# tricorder-teensy-mk-1_10.net
KiCad netlist of a schematic drawn in EAGLE
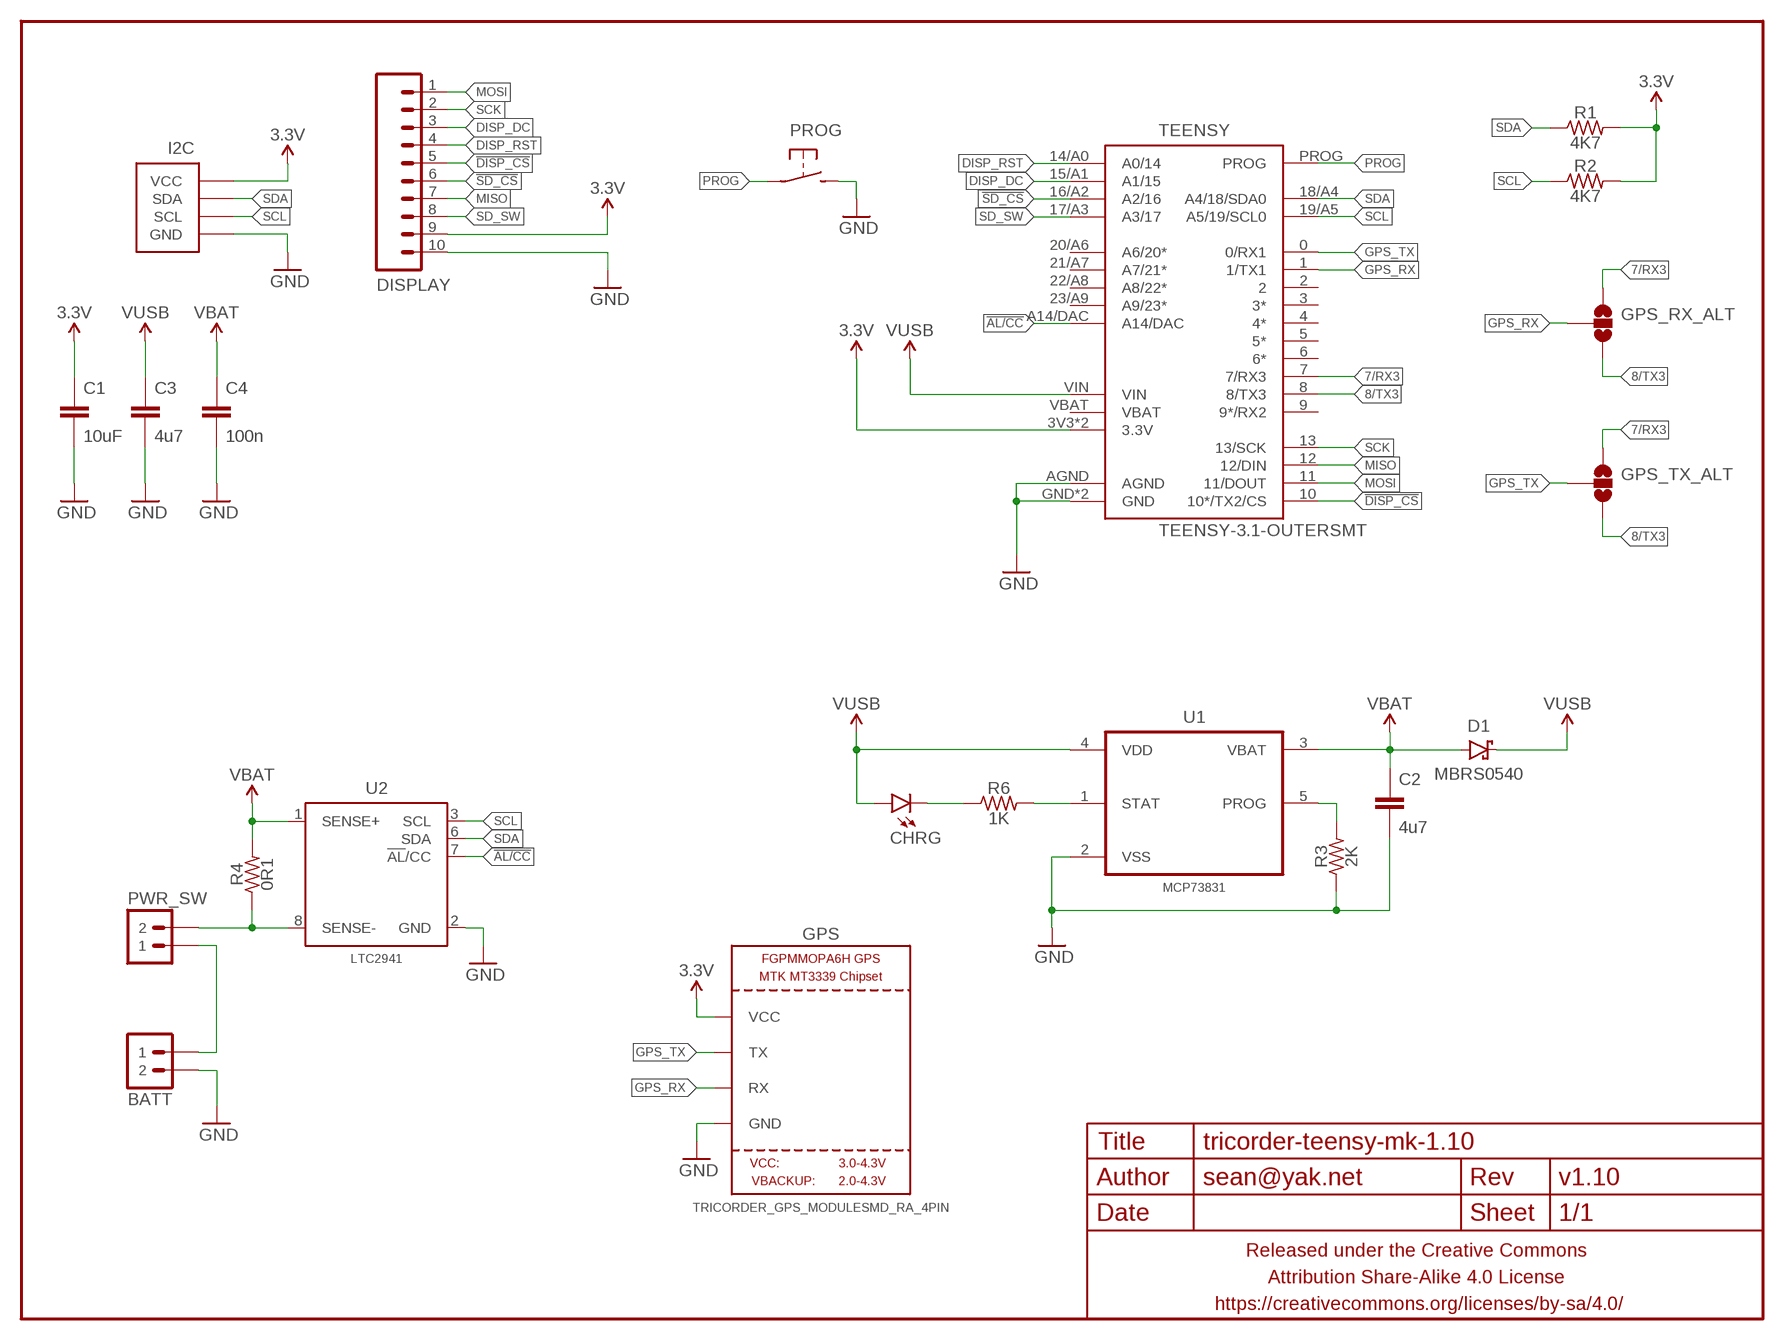
[diagram p0: schematic, sheet 1]

(export (version "E")
  (design (tool "Eeschema 10.0.6"))
  (components
    (comp (ref "BATT")
      (value "M02JST-2MM-SMT")
      (footprint "eagle-import:JST-2-SMD")
      (libsource (lib "eagle-import") (part "M02JST-2MM-SMT"))
    )
    (comp (ref "C1")
      (value "10uF")
      (footprint "eagle-import:C1210")
      (libsource (lib "eagle-import") (part "CAPACITOR-CERAMICC1210"))
    )
    (comp (ref "C2")
      (value "4u7")
      (footprint "eagle-import:C0603-TIGHTER")
      (libsource (lib "eagle-import") (part "CAPACITOR-CERAMICC0603-TIGHTER"))
    )
    (comp (ref "C3")
      (value "4u7")
      (footprint "eagle-import:C0603-TIGHTER")
      (libsource (lib "eagle-import") (part "CAPACITOR-CERAMICC0603-TIGHTER"))
    )
    (comp (ref "C4")
      (value "100n")
      (footprint "eagle-import:C0603-TIGHTER")
      (libsource (lib "eagle-import") (part "CAPACITOR-CERAMICC0603-TIGHTER"))
    )
    (comp (ref "CHRG")
      (value "LED0603-TIGHT")
      (footprint "eagle-import:LED-0603-TIGHT")
      (libsource (lib "eagle-import") (part "LED0603-TIGHT"))
    )
    (comp (ref "D1")
      (value "MBRS0540")
      (footprint "eagle-import:SOD123-SCHOTTKY")
      (libsource (lib "eagle-import") (part "DIODE-SCHOTTKYSOD123"))
    )
    (comp (ref "DISPLAY")
      (value "M10SMD_RA_2MM")
      (footprint "eagle-import:1X10_SMD_RA_MALE")
      (libsource (lib "eagle-import") (part "M10SMD_RA_2MM"))
    )
    (comp (ref "FRAME1")
      (value "FRAME-LETTERNO_PACKAGE")
      (footprint "eagle-import:DUMMY")
      (fields (field (name "DESIGNER") "sean@yak.net") (field (name "VERSION") "v1.10"))
      (libsource (lib "eagle-import") (part "FRAME-LETTERNO_PACKAGE"))
    )
    (comp (ref "GPS")
      (value "TRICORDER_GPS_MODULESMD_RA_4PIN")
      (footprint "eagle-import:TRICORDER_GPS_MODULE_RA_CONN_SMD_4PIN")
      (libsource (lib "eagle-import") (part "TRICORDER_GPS_MODULESMD_RA_4PIN"))
    )
    (comp (ref "GPS_RX_ALT")
      (value "JUMPER-PAD-3-NOFULL_BOX_SILK")
      (footprint "eagle-import:PAD-JUMPER-3-NO_YES_SILK_FULL_BOX")
      (libsource (lib "eagle-import") (part "JUMPER-PAD-3-NOFULL_BOX_SILK"))
    )
    (comp (ref "GPS_TX_ALT")
      (value "JUMPER-PAD-3-NOFULL_BOX_SILK")
      (footprint "eagle-import:PAD-JUMPER-3-NO_YES_SILK_FULL_BOX")
      (libsource (lib "eagle-import") (part "JUMPER-PAD-3-NOFULL_BOX_SILK"))
    )
    (comp (ref "I2C")
      (value "M04-I2CSMD_2MM_RA")
      (footprint "eagle-import:1X04_SMD_RA_2MM_I2C")
      (libsource (lib "eagle-import") (part "M04-I2CSMD_2MM_RA"))
    )
    (comp (ref "PROG")
      (value "SPST-NO-TACTCK-PTS840-GK")
      (footprint "eagle-import:TACTILE-SMD-CK-PTS840-GK")
      (libsource (lib "eagle-import") (part "SPST-NO-TACTCK-PTS840-GK"))
    )
    (comp (ref "PWR_SW")
      (value "M02JST-2MM-SMT")
      (footprint "eagle-import:JST-2-SMD")
      (libsource (lib "eagle-import") (part "M02JST-2MM-SMT"))
    )
    (comp (ref "R1")
      (value "4K7")
      (footprint "eagle-import:R0603-TIGHTER")
      (libsource (lib "eagle-import") (part "RESISTORR0603-TIGHTER"))
    )
    (comp (ref "R2")
      (value "4K7")
      (footprint "eagle-import:R0603-TIGHTER")
      (libsource (lib "eagle-import") (part "RESISTORR0603-TIGHTER"))
    )
    (comp (ref "R3")
      (value "2K")
      (footprint "eagle-import:R0603-TIGHTER")
      (libsource (lib "eagle-import") (part "RESISTORR0603-TIGHTER"))
    )
    (comp (ref "R4")
      (value "0R1")
      (footprint "eagle-import:R0603-TIGHTER")
      (libsource (lib "eagle-import") (part "RESISTORR0603-TIGHTER"))
    )
    (comp (ref "R6")
      (value "1K")
      (footprint "eagle-import:R0603-TIGHTER")
      (libsource (lib "eagle-import") (part "RESISTORR0603-TIGHTER"))
    )
    (comp (ref "TEENSY")
      (value "TEENSY-3.1-OUTERSMT")
      (footprint "eagle-import:TEENSY-3.1_SMT_BOTTOM_OUTERONLY")
      (libsource (lib "eagle-import") (part "TEENSY-3.1-OUTERSMT"))
    )
    (comp (ref "U1")
      (value "MCP73831")
      (footprint "eagle-import:SOT95P280X145-5N")
      (fields (field (name "MPN") "MCP73831T-2ACI/OT"))
      (libsource (lib "eagle-import") (part "MCP73831T-2ACI/OT"))
    )
    (comp (ref "U2")
      (value "LTC2941")
      (footprint "eagle-import:MSOP-8")
      (libsource (lib "eagle-import") (part "LTC2941MSOP-8"))
    )
  )
  (nets
    (net (code "1") (name "/~{AL{slash}CC}") (class "Default")
      (node (ref "TEENSY") (pin "A14/DAC") (pinfunction "A14/DAC_A14/DAC") (pintype "bidirectional"))
      (node (ref "U2") (pin "7") (pinfunction "~{AL}/CC_7") (pintype "bidirectional"))
    )
    (net (code "2") (name "/~{DISP_CS}") (class "Default")
      (node (ref "DISPLAY") (pin "5") (pinfunction "5_5") (pintype "passive"))
      (node (ref "TEENSY") (pin "10") (pinfunction "10*/TX2/CS_10") (pintype "bidirectional"))
    )
    (net (code "3") (name "/~{SD_CS}") (class "Default")
      (node (ref "DISPLAY") (pin "6") (pinfunction "6_6") (pintype "passive"))
      (node (ref "TEENSY") (pin "16/A2") (pinfunction "A2/16_16/A2") (pintype "bidirectional"))
    )
    (net (code "4") (name "3.3V") (class "Default")
      (node (ref "C1") (pin "1") (pinfunction "1_1") (pintype "passive"))
      (node (ref "DISPLAY") (pin "9") (pinfunction "9_9") (pintype "passive"))
      (node (ref "GPS") (pin "VCC") (pinfunction "VCC_VCC") (pintype "bidirectional"))
      (node (ref "I2C") (pin "VCC") (pinfunction "VCC_VCC") (pintype "bidirectional"))
      (node (ref "R1") (pin "2") (pinfunction "2_2") (pintype "passive"))
      (node (ref "R2") (pin "2") (pinfunction "2_2") (pintype "passive"))
      (node (ref "TEENSY") (pin "3V3") (pinfunction "3.3V_3V3") (pintype "bidirectional"))
      (node (ref "TEENSY") (pin "3V3@1") (pinfunction "3.3V_3V3@1") (pintype "bidirectional"))
    )
    (net (code "5") (name "7{slash}RX3") (class "Default")
      (node (ref "GPS_RX_ALT") (pin "1") (pinfunction "1_1") (pintype "passive"))
      (node (ref "GPS_TX_ALT") (pin "1") (pinfunction "1_1") (pintype "passive"))
      (node (ref "TEENSY") (pin "7") (pinfunction "7/RX3_7") (pintype "bidirectional"))
    )
    (net (code "6") (name "8{slash}TX3") (class "Default")
      (node (ref "GPS_RX_ALT") (pin "3") (pinfunction "3_3") (pintype "passive"))
      (node (ref "GPS_TX_ALT") (pin "3") (pinfunction "3_3") (pintype "passive"))
      (node (ref "TEENSY") (pin "8") (pinfunction "8/TX3_8") (pintype "bidirectional"))
    )
    (net (code "7") (name "DISP_DC") (class "Default")
      (node (ref "DISPLAY") (pin "3") (pinfunction "3_3") (pintype "passive"))
      (node (ref "TEENSY") (pin "15/A1") (pinfunction "A1/15_15/A1") (pintype "bidirectional"))
    )
    (net (code "8") (name "DISP_RST") (class "Default")
      (node (ref "DISPLAY") (pin "4") (pinfunction "4_4") (pintype "passive"))
      (node (ref "TEENSY") (pin "14/A0") (pinfunction "A0/14_14/A0") (pintype "bidirectional"))
    )
    (net (code "9") (name "GND") (class "Default")
      (node (ref "BATT") (pin "1") (pinfunction "2_1") (pintype "passive"))
      (node (ref "C1") (pin "2") (pinfunction "2_2") (pintype "passive"))
      (node (ref "C2") (pin "2") (pinfunction "2_2") (pintype "passive"))
      (node (ref "C3") (pin "2") (pinfunction "2_2") (pintype "passive"))
      (node (ref "C4") (pin "2") (pinfunction "2_2") (pintype "passive"))
      (node (ref "DISPLAY") (pin "10") (pinfunction "10_10") (pintype "passive"))
      (node (ref "GPS") (pin "GND") (pinfunction "GND_GND") (pintype "bidirectional"))
      (node (ref "I2C") (pin "GND") (pinfunction "GND_GND") (pintype "bidirectional"))
      (node (ref "PROG") (pin "3") (pinfunction "2_3") (pintype "passive"))
      (node (ref "PROG") (pin "4") (pinfunction "2_4") (pintype "passive"))
      (node (ref "R3") (pin "1") (pinfunction "1_1") (pintype "passive"))
      (node (ref "TEENSY") (pin "AGND") (pinfunction "AGND_AGND") (pintype "bidirectional"))
      (node (ref "TEENSY") (pin "GND") (pinfunction "GND_GND") (pintype "bidirectional"))
      (node (ref "TEENSY") (pin "GND@1") (pinfunction "GND_GND@1") (pintype "bidirectional"))
      (node (ref "U1") (pin "2") (pinfunction "VSS_2") (pintype "power_in"))
      (node (ref "U2") (pin "2") (pinfunction "GND_2") (pintype "bidirectional"))
    )
    (net (code "10") (name "GPS_RX") (class "Default")
      (node (ref "GPS") (pin "RX") (pinfunction "RX_RX") (pintype "bidirectional"))
      (node (ref "GPS_RX_ALT") (pin "2") (pinfunction "2_2") (pintype "passive"))
      (node (ref "TEENSY") (pin "1") (pinfunction "1/TX1_1") (pintype "bidirectional"))
    )
    (net (code "11") (name "GPS_TX") (class "Default")
      (node (ref "GPS") (pin "TX") (pinfunction "TX_TX") (pintype "bidirectional"))
      (node (ref "GPS_TX_ALT") (pin "2") (pinfunction "2_2") (pintype "passive"))
      (node (ref "TEENSY") (pin "0") (pinfunction "0/RX1_0") (pintype "bidirectional"))
    )
    (net (code "12") (name "MISO") (class "Default")
      (node (ref "DISPLAY") (pin "7") (pinfunction "7_7") (pintype "passive"))
      (node (ref "TEENSY") (pin "12") (pinfunction "12/DIN_12") (pintype "bidirectional"))
    )
    (net (code "13") (name "MOSI") (class "Default")
      (node (ref "DISPLAY") (pin "1") (pinfunction "1_1") (pintype "passive"))
      (node (ref "TEENSY") (pin "11") (pinfunction "11/DOUT_11") (pintype "bidirectional"))
    )
    (net (code "14") (name "Net-(BATT-1)") (class "Default")
      (node (ref "BATT") (pin "2") (pinfunction "1_2") (pintype "passive"))
      (node (ref "PWR_SW") (pin "2") (pinfunction "1_2") (pintype "passive"))
    )
    (net (code "15") (name "Net-(CHRG-PadC)") (class "Default")
      (node (ref "CHRG") (pin "C") (pinfunction "C_C") (pintype "passive"))
      (node (ref "R6") (pin "1") (pinfunction "1_1") (pintype "passive"))
    )
    (net (code "16") (name "Net-(PWR_SW-2)") (class "Default")
      (node (ref "PWR_SW") (pin "1") (pinfunction "2_1") (pintype "passive"))
      (node (ref "R4") (pin "1") (pinfunction "1_1") (pintype "passive"))
      (node (ref "U2") (pin "8") (pinfunction "SENSE-_8") (pintype "bidirectional"))
    )
    (net (code "17") (name "Net-(U1-PROG)") (class "Default")
      (node (ref "R3") (pin "2") (pinfunction "2_2") (pintype "passive"))
      (node (ref "U1") (pin "5") (pinfunction "PROG_5") (pintype "input"))
    )
    (net (code "18") (name "Net-(U1-STAT)") (class "Default")
      (node (ref "R6") (pin "2") (pinfunction "2_2") (pintype "passive"))
      (node (ref "U1") (pin "1") (pinfunction "STAT_1") (pintype "output"))
    )
    (net (code "19") (name "PROG") (class "Default")
      (node (ref "PROG") (pin "1") (pinfunction "1_1") (pintype "passive"))
      (node (ref "PROG") (pin "2") (pinfunction "1_2") (pintype "passive"))
      (node (ref "TEENSY") (pin "PROG") (pinfunction "PROG_PROG") (pintype "bidirectional"))
    )
    (net (code "20") (name "SCK") (class "Default")
      (node (ref "DISPLAY") (pin "2") (pinfunction "2_2") (pintype "passive"))
      (node (ref "TEENSY") (pin "13") (pinfunction "13/SCK_13") (pintype "bidirectional"))
    )
    (net (code "21") (name "SCL") (class "Default")
      (node (ref "I2C") (pin "SCL") (pinfunction "SCL_SCL") (pintype "bidirectional"))
      (node (ref "R2") (pin "1") (pinfunction "1_1") (pintype "passive"))
      (node (ref "TEENSY") (pin "19/A5") (pinfunction "A5/19/SCL0_19/A5") (pintype "bidirectional"))
      (node (ref "U2") (pin "3") (pinfunction "SCL_3") (pintype "bidirectional"))
    )
    (net (code "22") (name "SDA") (class "Default")
      (node (ref "I2C") (pin "SDA") (pinfunction "SDA_SDA") (pintype "bidirectional"))
      (node (ref "R1") (pin "1") (pinfunction "1_1") (pintype "passive"))
      (node (ref "TEENSY") (pin "18/A4") (pinfunction "A4/18/SDA0_18/A4") (pintype "bidirectional"))
      (node (ref "U2") (pin "6") (pinfunction "SDA_6") (pintype "bidirectional"))
    )
    (net (code "23") (name "SD_SW") (class "Default")
      (node (ref "DISPLAY") (pin "8") (pinfunction "8_8") (pintype "passive"))
      (node (ref "TEENSY") (pin "17/A3") (pinfunction "A3/17_17/A3") (pintype "bidirectional"))
    )
    (net (code "24") (name "VBAT") (class "Default")
      (node (ref "C2") (pin "1") (pinfunction "1_1") (pintype "passive"))
      (node (ref "C4") (pin "1") (pinfunction "1_1") (pintype "passive"))
      (node (ref "D1") (pin "A") (pinfunction "A_A") (pintype "passive"))
      (node (ref "R4") (pin "2") (pinfunction "2_2") (pintype "passive"))
      (node (ref "U1") (pin "3") (pinfunction "VBAT_3") (pintype "output"))
      (node (ref "U2") (pin "1") (pinfunction "SENSE+_1") (pintype "bidirectional"))
    )
    (net (code "25") (name "VUSB") (class "Default")
      (node (ref "C3") (pin "1") (pinfunction "1_1") (pintype "passive"))
      (node (ref "CHRG") (pin "A") (pinfunction "A_A") (pintype "passive"))
      (node (ref "D1") (pin "C") (pinfunction "C_C") (pintype "passive"))
      (node (ref "TEENSY") (pin "VIN") (pinfunction "VIN_VIN") (pintype "bidirectional"))
      (node (ref "U1") (pin "4") (pinfunction "VDD_4") (pintype "power_in"))
    )
    (net (code "26") (name "unconnected-(TEENSY-3*-Pad3)") (class "Default")
      (node (ref "TEENSY") (pin "3") (pinfunction "3*_3") (pintype "bidirectional"))
    )
    (net (code "27") (name "unconnected-(TEENSY-4*-Pad4)") (class "Default")
      (node (ref "TEENSY") (pin "4") (pinfunction "4*_4") (pintype "bidirectional"))
    )
    (net (code "28") (name "unconnected-(TEENSY-5*-Pad5)") (class "Default")
      (node (ref "TEENSY") (pin "5") (pinfunction "5*_5") (pintype "bidirectional"))
    )
    (net (code "29") (name "unconnected-(TEENSY-6*-Pad6)") (class "Default")
      (node (ref "TEENSY") (pin "6") (pinfunction "6*_6") (pintype "bidirectional"))
    )
    (net (code "30") (name "unconnected-(TEENSY-9*{slash}RX2-Pad9)") (class "Default")
      (node (ref "TEENSY") (pin "9") (pinfunction "9*/RX2_9") (pintype "bidirectional"))
    )
    (net (code "31") (name "unconnected-(TEENSY-A6{slash}20*-Pad20{slash}A6)") (class "Default")
      (node (ref "TEENSY") (pin "20/A6") (pinfunction "A6/20*_20/A6") (pintype "bidirectional"))
    )
    (net (code "32") (name "unconnected-(TEENSY-A7{slash}21*-Pad21{slash}A7)") (class "Default")
      (node (ref "TEENSY") (pin "21/A7") (pinfunction "A7/21*_21/A7") (pintype "bidirectional"))
    )
    (net (code "33") (name "unconnected-(TEENSY-A8{slash}22*-Pad22{slash}A8)") (class "Default")
      (node (ref "TEENSY") (pin "22/A8") (pinfunction "A8/22*_22/A8") (pintype "bidirectional"))
    )
    (net (code "34") (name "unconnected-(TEENSY-A9{slash}23*-Pad23{slash}A9)") (class "Default")
      (node (ref "TEENSY") (pin "23/A9") (pinfunction "A9/23*_23/A9") (pintype "bidirectional"))
    )
    (net (code "35") (name "unconnected-(TEENSY-Pad2)") (class "Default")
      (node (ref "TEENSY") (pin "2") (pinfunction "2_2") (pintype "bidirectional"))
    )
    (net (code "36") (name "unconnected-(TEENSY-PadVBAT)") (class "Default")
      (node (ref "TEENSY") (pin "VBAT") (pinfunction "VBAT_VBAT") (pintype "bidirectional"))
    )
  )
)
